# Sensors.net
KiCad netlist of a schematic drawn in Altium Designer
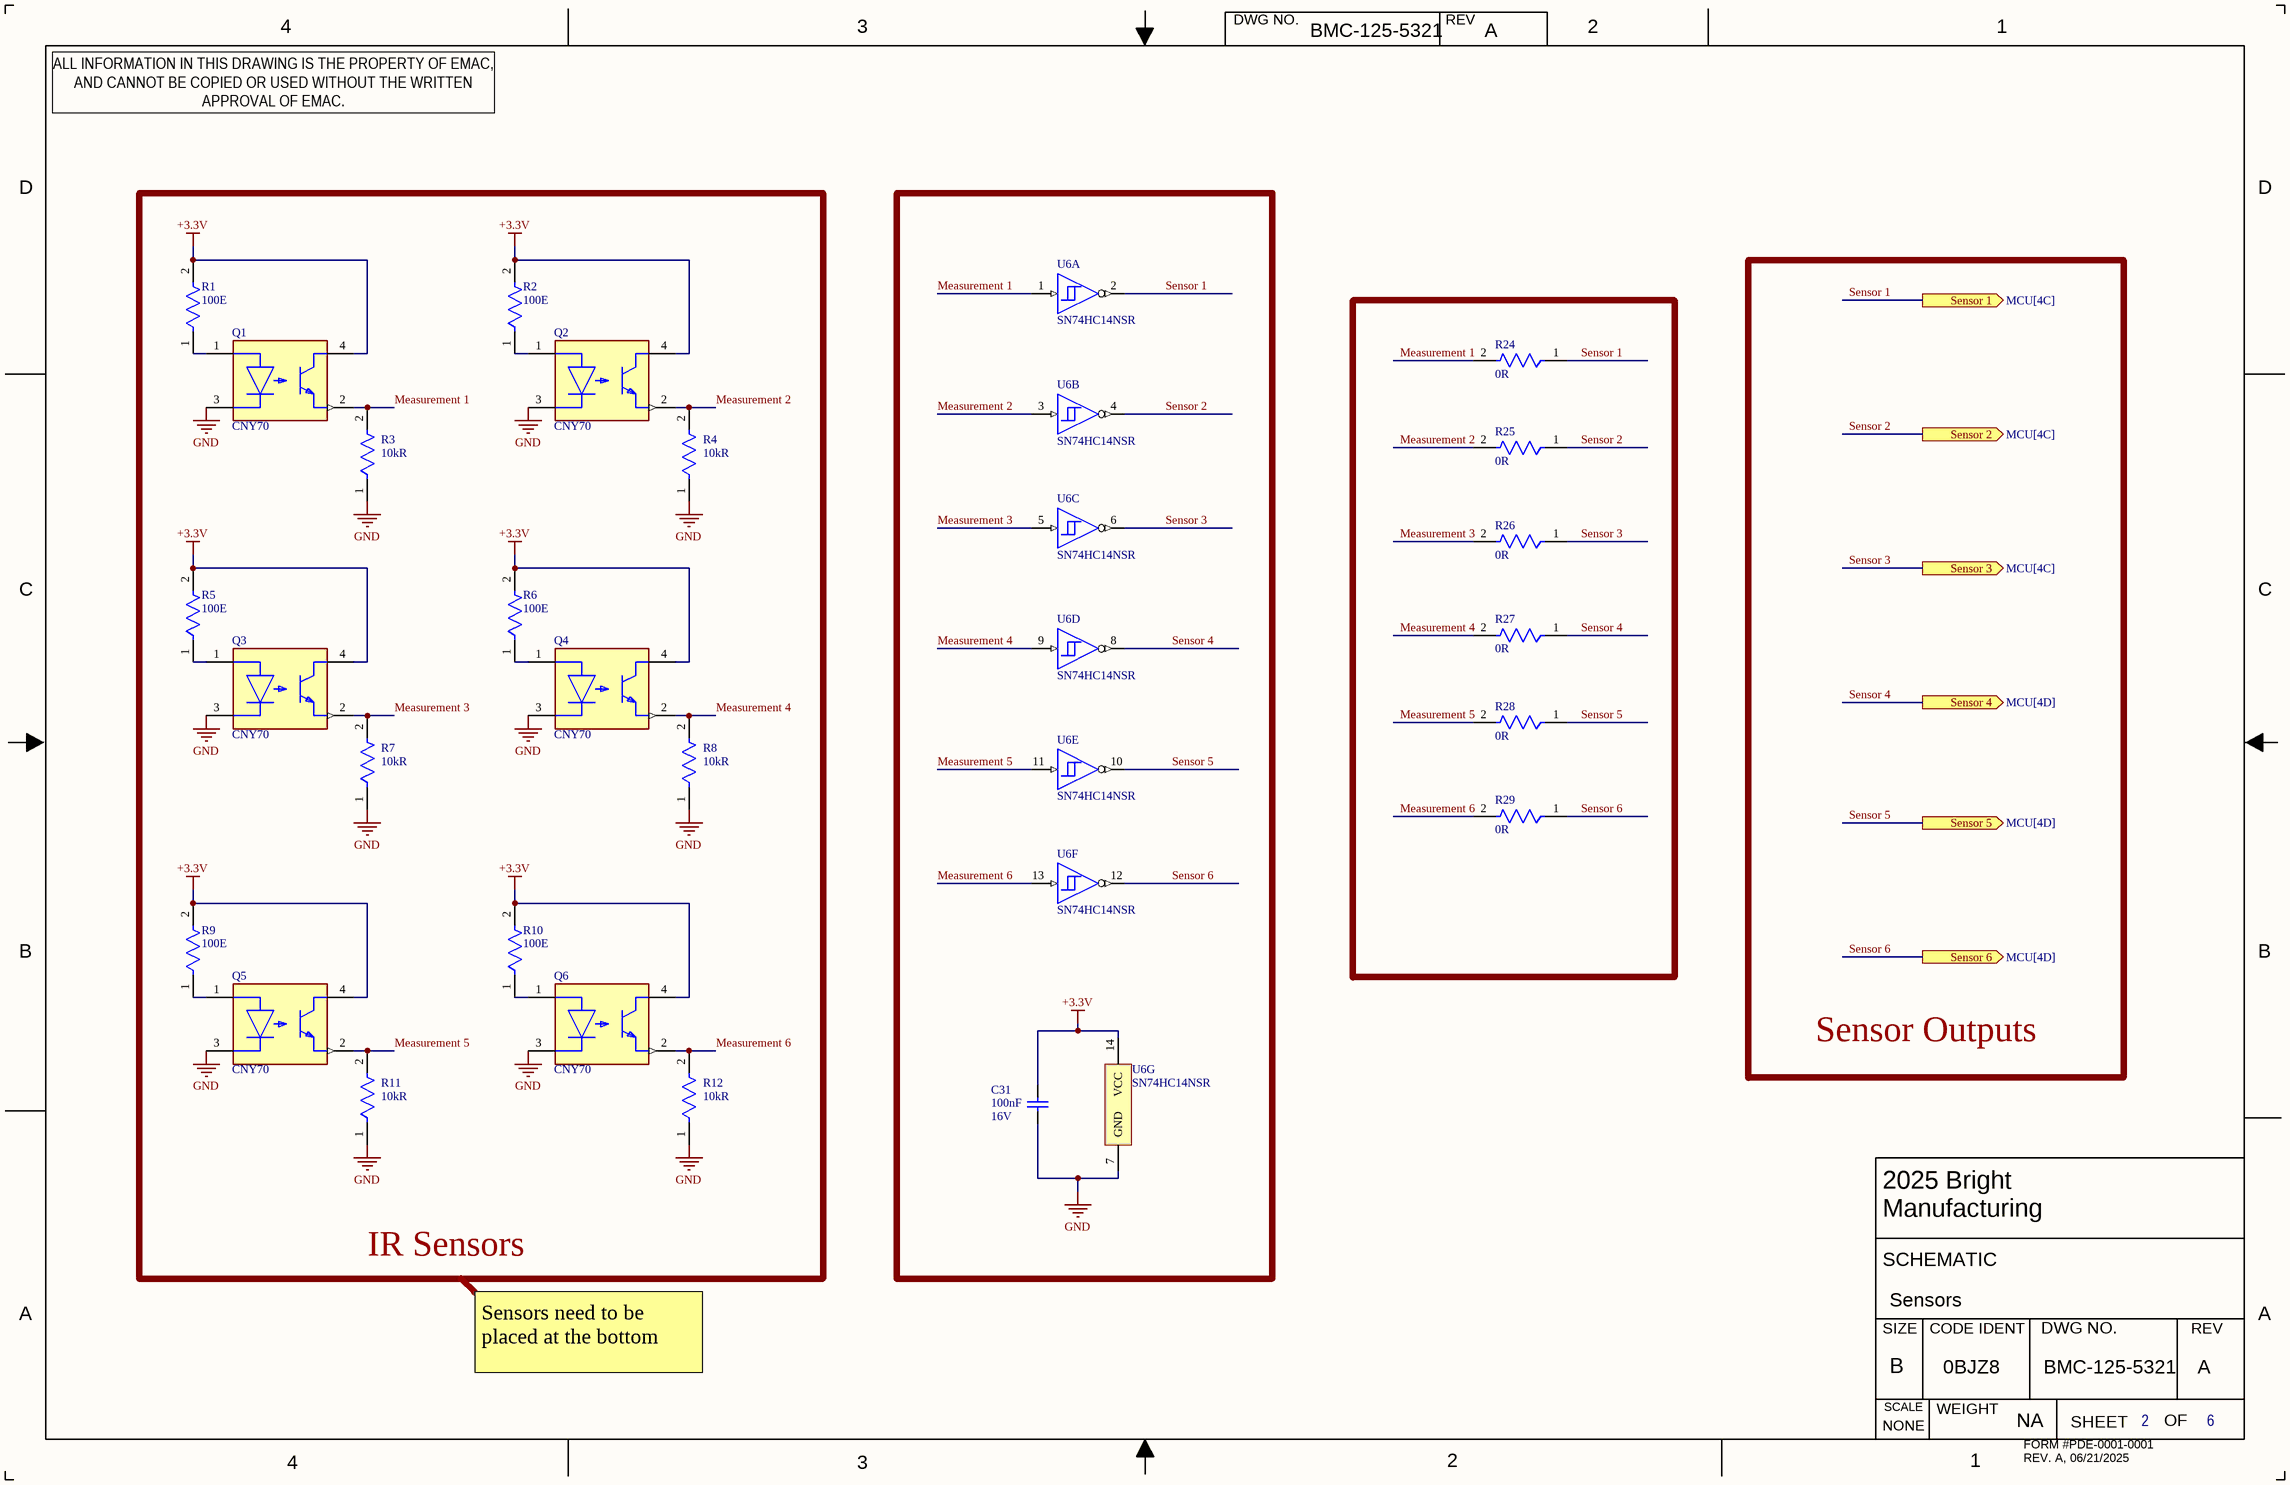
[diagram p0: Sensors.SchDoc]

(export (version "E")
  (design (tool "Eeschema 10.0.6"))
  (components
    (comp (ref "C31")
      (value "100nF")
      (footprint "CAPC1608X90X35LL15T15")
      (fields (field (name "RATED DC VOLTAGE (URDC)") "16V") (field (name "Comment") "0.1uF 16V 0603"))
      (libsource (lib "2025 Bright Manufacturing Challenge") (part "CAP"))
    )
    (comp (ref "Q1")
      (value "CNY70")
      (footprint "FP-6_544-5062_01-4-MFG")
      (description "Diffuse Photoelectric Sensor, 0mm Min, 5mm Max, 0.30-1mA, 1-Channel, Square, Through Hole Mount")
      (libsource (lib "2025 Bright Manufacturing Challenge") (part "76cf3928268f24b4c386281b57b36cb"))
    )
    (comp (ref "Q2")
      (value "CNY70")
      (footprint "FP-6_544-5062_01-4-MFG")
      (description "Diffuse Photoelectric Sensor, 0mm Min, 5mm Max, 0.30-1mA, 1-Channel, Square, Through Hole Mount")
      (libsource (lib "2025 Bright Manufacturing Challenge") (part "76cf3928268f24b4c386281b57b36cb"))
    )
    (comp (ref "Q3")
      (value "CNY70")
      (footprint "FP-6_544-5062_01-4-MFG")
      (description "Diffuse Photoelectric Sensor, 0mm Min, 5mm Max, 0.30-1mA, 1-Channel, Square, Through Hole Mount")
      (libsource (lib "2025 Bright Manufacturing Challenge") (part "76cf3928268f24b4c386281b57b36cb"))
    )
    (comp (ref "Q4")
      (value "CNY70")
      (footprint "FP-6_544-5062_01-4-MFG")
      (description "Diffuse Photoelectric Sensor, 0mm Min, 5mm Max, 0.30-1mA, 1-Channel, Square, Through Hole Mount")
      (libsource (lib "2025 Bright Manufacturing Challenge") (part "76cf3928268f24b4c386281b57b36cb"))
    )
    (comp (ref "Q5")
      (value "CNY70")
      (footprint "FP-6_544-5062_01-4-MFG")
      (description "Diffuse Photoelectric Sensor, 0mm Min, 5mm Max, 0.30-1mA, 1-Channel, Square, Through Hole Mount")
      (libsource (lib "2025 Bright Manufacturing Challenge") (part "76cf3928268f24b4c386281b57b36cb"))
    )
    (comp (ref "Q6")
      (value "CNY70")
      (footprint "FP-6_544-5062_01-4-MFG")
      (description "Diffuse Photoelectric Sensor, 0mm Min, 5mm Max, 0.30-1mA, 1-Channel, Square, Through Hole Mount")
      (libsource (lib "2025 Bright Manufacturing Challenge") (part "76cf3928268f24b4c386281b57b36cb"))
    )
    (comp (ref "R1")
      (value "100E")
      (footprint "FP-RT0603-MFG")
      (description "RES SMD 100 OHM 0.5% 1/10W 0603")
      (fields
        (field (name "TOLERANCE") "0.005")
        (field (name "OCTOPART") "https://octopart.com/rt0603dre07100rl-yageo-1441481")
      )
      (libsource (lib "Altium Content Vault") (part "1029c3af85768c4190bb7ad29bc67b5"))
    )
    (comp (ref "R2")
      (value "100E")
      (footprint "FP-RT0603-MFG")
      (description "RES SMD 100 OHM 0.5% 1/10W 0603")
      (fields
        (field (name "TOLERANCE") "0.005")
        (field (name "OCTOPART") "https://octopart.com/rt0603dre07100rl-yageo-1441481")
      )
      (libsource (lib "Altium Content Vault") (part "1029c3af85768c4190bb7ad29bc67b5"))
    )
    (comp (ref "R3")
      (value "10kR")
      (footprint "RESC1608X55X25ML10T15")
      (fields
        (field (name "TOLERANCE") "5%")
        (field (name "POWER") "100mW")
        (field (name "Comment") "10KOhm 0603")
      )
      (libsource (lib "2025 Bright Manufacturing Challenge") (part "1029c3af85768c4190bb7ad29bc67b5"))
    )
    (comp (ref "R4")
      (value "10kR")
      (footprint "RESC1608X55X25ML10T15")
      (fields
        (field (name "TOLERANCE") "5%")
        (field (name "POWER") "100mW")
        (field (name "Comment") "10KOhm 0603")
      )
      (libsource (lib "2025 Bright Manufacturing Challenge") (part "1029c3af85768c4190bb7ad29bc67b5"))
    )
    (comp (ref "R5")
      (value "100E")
      (footprint "FP-RT0603-MFG")
      (description "RES SMD 100 OHM 0.5% 1/10W 0603")
      (fields
        (field (name "TOLERANCE") "0.005")
        (field (name "OCTOPART") "https://octopart.com/rt0603dre07100rl-yageo-1441481")
      )
      (libsource (lib "Altium Content Vault") (part "1029c3af85768c4190bb7ad29bc67b5"))
    )
    (comp (ref "R6")
      (value "100E")
      (footprint "FP-RT0603-MFG")
      (description "RES SMD 100 OHM 0.5% 1/10W 0603")
      (fields
        (field (name "TOLERANCE") "0.005")
        (field (name "OCTOPART") "https://octopart.com/rt0603dre07100rl-yageo-1441481")
      )
      (libsource (lib "Altium Content Vault") (part "1029c3af85768c4190bb7ad29bc67b5"))
    )
    (comp (ref "R7")
      (value "10kR")
      (footprint "RESC1608X55X25ML10T15")
      (fields
        (field (name "TOLERANCE") "5%")
        (field (name "POWER") "100mW")
        (field (name "Comment") "10KOhm 0603")
      )
      (libsource (lib "2025 Bright Manufacturing Challenge") (part "1029c3af85768c4190bb7ad29bc67b5"))
    )
    (comp (ref "R8")
      (value "10kR")
      (footprint "RESC1608X55X25ML10T15")
      (fields
        (field (name "TOLERANCE") "5%")
        (field (name "POWER") "100mW")
        (field (name "Comment") "10KOhm 0603")
      )
      (libsource (lib "2025 Bright Manufacturing Challenge") (part "1029c3af85768c4190bb7ad29bc67b5"))
    )
    (comp (ref "R9")
      (value "100E")
      (footprint "FP-RT0603-MFG")
      (description "RES SMD 100 OHM 0.5% 1/10W 0603")
      (fields
        (field (name "TOLERANCE") "0.005")
        (field (name "OCTOPART") "https://octopart.com/rt0603dre07100rl-yageo-1441481")
      )
      (libsource (lib "Altium Content Vault") (part "1029c3af85768c4190bb7ad29bc67b5"))
    )
    (comp (ref "R10")
      (value "100E")
      (footprint "FP-RT0603-MFG")
      (description "RES SMD 100 OHM 0.5% 1/10W 0603")
      (fields
        (field (name "TOLERANCE") "0.005")
        (field (name "OCTOPART") "https://octopart.com/rt0603dre07100rl-yageo-1441481")
      )
      (libsource (lib "Altium Content Vault") (part "1029c3af85768c4190bb7ad29bc67b5"))
    )
    (comp (ref "R11")
      (value "10kR")
      (footprint "RESC1608X55X25ML10T15")
      (fields
        (field (name "TOLERANCE") "5%")
        (field (name "POWER") "100mW")
        (field (name "Comment") "10KOhm 0603")
      )
      (libsource (lib "2025 Bright Manufacturing Challenge") (part "1029c3af85768c4190bb7ad29bc67b5"))
    )
    (comp (ref "R12")
      (value "10kR")
      (footprint "RESC1608X55X25ML10T15")
      (fields
        (field (name "TOLERANCE") "5%")
        (field (name "POWER") "100mW")
        (field (name "Comment") "10KOhm 0603")
      )
      (libsource (lib "2025 Bright Manufacturing Challenge") (part "1029c3af85768c4190bb7ad29bc67b5"))
    )
    (comp (ref "R24")
      (value "0R")
      (footprint "FP-RC0603-MFG")
      (description "RES SMD 0 OHM JUMPER 1/10W 0603")
      (fields
        (field (name "TOLERANCE") "1%")
        (field (name "OCTOPART") "https://octopart.com/rc0603fr-070rl-yageo-1180803")
      )
      (libsource (lib "Altium Content Vault") (part "1029c3af85768c4190bb7ad29bc67b5"))
    )
    (comp (ref "R25")
      (value "0R")
      (footprint "FP-RC0603-MFG")
      (description "RES SMD 0 OHM JUMPER 1/10W 0603")
      (fields
        (field (name "TOLERANCE") "1%")
        (field (name "OCTOPART") "https://octopart.com/rc0603fr-070rl-yageo-1180803")
      )
      (libsource (lib "Altium Content Vault") (part "1029c3af85768c4190bb7ad29bc67b5"))
    )
    (comp (ref "R26")
      (value "0R")
      (footprint "FP-RC0603-MFG")
      (description "RES SMD 0 OHM JUMPER 1/10W 0603")
      (fields
        (field (name "TOLERANCE") "1%")
        (field (name "OCTOPART") "https://octopart.com/rc0603fr-070rl-yageo-1180803")
      )
      (libsource (lib "Altium Content Vault") (part "1029c3af85768c4190bb7ad29bc67b5"))
    )
    (comp (ref "R27")
      (value "0R")
      (footprint "FP-RC0603-MFG")
      (description "RES SMD 0 OHM JUMPER 1/10W 0603")
      (fields
        (field (name "TOLERANCE") "1%")
        (field (name "OCTOPART") "https://octopart.com/rc0603fr-070rl-yageo-1180803")
      )
      (libsource (lib "Altium Content Vault") (part "1029c3af85768c4190bb7ad29bc67b5"))
    )
    (comp (ref "R28")
      (value "0R")
      (footprint "FP-RC0603-MFG")
      (description "RES SMD 0 OHM JUMPER 1/10W 0603")
      (fields
        (field (name "TOLERANCE") "1%")
        (field (name "OCTOPART") "https://octopart.com/rc0603fr-070rl-yageo-1180803")
      )
      (libsource (lib "Altium Content Vault") (part "1029c3af85768c4190bb7ad29bc67b5"))
    )
    (comp (ref "R29")
      (value "0R")
      (footprint "FP-RC0603-MFG")
      (description "RES SMD 0 OHM JUMPER 1/10W 0603")
      (fields
        (field (name "TOLERANCE") "1%")
        (field (name "OCTOPART") "https://octopart.com/rc0603fr-070rl-yageo-1180803")
      )
      (libsource (lib "Altium Content Vault") (part "1029c3af85768c4190bb7ad29bc67b5"))
    )
    (comp (ref "U6")
      (value "SN74HC14NSR")
      (footprint "NS0014A_N")
      (description "Inverter, HC Series, 6-Func, 1-Input, CMOS, PDSO14")
      (libsource (lib "2025 Bright Manufacturing Challenge") (part "TI-CD_SNX4XXXXXX4X_19A-14-SCHMITT"))
    )
  )
  (nets
    (net (code "1") (name "+3.3V") (class "Default")
      (node (ref "C31") (pin "2") (pinfunction "2_2") (pintype "passive"))
      (node (ref "Q1") (pin "4") (pinfunction "C_4") (pintype "passive"))
      (node (ref "Q2") (pin "4") (pinfunction "C_4") (pintype "passive"))
      (node (ref "Q3") (pin "4") (pinfunction "C_4") (pintype "passive"))
      (node (ref "Q4") (pin "4") (pinfunction "C_4") (pintype "passive"))
      (node (ref "Q5") (pin "4") (pinfunction "C_4") (pintype "passive"))
      (node (ref "Q6") (pin "4") (pinfunction "C_4") (pintype "passive"))
      (node (ref "R1") (pin "2") (pinfunction "2_2") (pintype "passive"))
      (node (ref "R10") (pin "2") (pinfunction "2_2") (pintype "passive"))
      (node (ref "R2") (pin "2") (pinfunction "2_2") (pintype "passive"))
      (node (ref "R5") (pin "2") (pinfunction "2_2") (pintype "passive"))
      (node (ref "R6") (pin "2") (pinfunction "2_2") (pintype "passive"))
      (node (ref "R9") (pin "2") (pinfunction "2_2") (pintype "passive"))
      (node (ref "U6") (pin "14") (pinfunction "VCC_14") (pintype "power_in"))
    )
    (net (code "2") (name "/Measurement 1") (class "Default")
      (node (ref "Q1") (pin "2") (pinfunction "E_2") (pintype "output"))
      (node (ref "R24") (pin "2") (pinfunction "2_2") (pintype "passive"))
      (node (ref "R3") (pin "2") (pinfunction "2_2") (pintype "passive"))
      (node (ref "U6") (pin "1") (pinfunction "1A_1") (pintype "input"))
    )
    (net (code "3") (name "/Measurement 2") (class "Default")
      (node (ref "Q2") (pin "2") (pinfunction "E_2") (pintype "output"))
      (node (ref "R25") (pin "2") (pinfunction "2_2") (pintype "passive"))
      (node (ref "R4") (pin "2") (pinfunction "2_2") (pintype "passive"))
      (node (ref "U6") (pin "3") (pinfunction "2A_3") (pintype "input"))
    )
    (net (code "4") (name "/Measurement 3") (class "Default")
      (node (ref "Q3") (pin "2") (pinfunction "E_2") (pintype "output"))
      (node (ref "R26") (pin "2") (pinfunction "2_2") (pintype "passive"))
      (node (ref "R7") (pin "2") (pinfunction "2_2") (pintype "passive"))
      (node (ref "U6") (pin "5") (pinfunction "3A_5") (pintype "input"))
    )
    (net (code "5") (name "/Measurement 4") (class "Default")
      (node (ref "Q4") (pin "2") (pinfunction "E_2") (pintype "output"))
      (node (ref "R27") (pin "2") (pinfunction "2_2") (pintype "passive"))
      (node (ref "R8") (pin "2") (pinfunction "2_2") (pintype "passive"))
      (node (ref "U6") (pin "9") (pinfunction "4A_9") (pintype "input"))
    )
    (net (code "6") (name "/Measurement 5") (class "Default")
      (node (ref "Q5") (pin "2") (pinfunction "E_2") (pintype "output"))
      (node (ref "R11") (pin "2") (pinfunction "2_2") (pintype "passive"))
      (node (ref "R28") (pin "2") (pinfunction "2_2") (pintype "passive"))
      (node (ref "U6") (pin "11") (pinfunction "5A_11") (pintype "input"))
    )
    (net (code "7") (name "/Measurement 6") (class "Default")
      (node (ref "Q6") (pin "2") (pinfunction "E_2") (pintype "output"))
      (node (ref "R12") (pin "2") (pinfunction "2_2") (pintype "passive"))
      (node (ref "R29") (pin "2") (pinfunction "2_2") (pintype "passive"))
      (node (ref "U6") (pin "13") (pinfunction "6A_13") (pintype "input"))
    )
    (net (code "8") (name "/Sensor 1") (class "Default")
      (node (ref "R24") (pin "1") (pinfunction "1_1") (pintype "passive"))
      (node (ref "U6") (pin "2") (pinfunction "~{1Y}_2") (pintype "output"))
    )
    (net (code "9") (name "/Sensor 2") (class "Default")
      (node (ref "R25") (pin "1") (pinfunction "1_1") (pintype "passive"))
      (node (ref "U6") (pin "4") (pinfunction "~{2Y}_4") (pintype "output"))
    )
    (net (code "10") (name "/Sensor 3") (class "Default")
      (node (ref "R26") (pin "1") (pinfunction "1_1") (pintype "passive"))
      (node (ref "U6") (pin "6") (pinfunction "~{3Y}_6") (pintype "output"))
    )
    (net (code "11") (name "/Sensor 4") (class "Default")
      (node (ref "R27") (pin "1") (pinfunction "1_1") (pintype "passive"))
      (node (ref "U6") (pin "8") (pinfunction "~{4Y}_8") (pintype "output"))
    )
    (net (code "12") (name "/Sensor 5") (class "Default")
      (node (ref "R28") (pin "1") (pinfunction "1_1") (pintype "passive"))
      (node (ref "U6") (pin "10") (pinfunction "~{5Y}_10") (pintype "output"))
    )
    (net (code "13") (name "/Sensor 6") (class "Default")
      (node (ref "R29") (pin "1") (pinfunction "1_1") (pintype "passive"))
      (node (ref "U6") (pin "12") (pinfunction "~{6Y}_12") (pintype "output"))
    )
    (net (code "14") (name "GND") (class "Default")
      (node (ref "C31") (pin "1") (pinfunction "1_1") (pintype "passive"))
      (node (ref "Q1") (pin "3") (pinfunction "C_3") (pintype "passive"))
      (node (ref "Q2") (pin "3") (pinfunction "C_3") (pintype "passive"))
      (node (ref "Q3") (pin "3") (pinfunction "C_3") (pintype "passive"))
      (node (ref "Q4") (pin "3") (pinfunction "C_3") (pintype "passive"))
      (node (ref "Q5") (pin "3") (pinfunction "C_3") (pintype "passive"))
      (node (ref "Q6") (pin "3") (pinfunction "C_3") (pintype "passive"))
      (node (ref "R11") (pin "1") (pinfunction "1_1") (pintype "passive"))
      (node (ref "R12") (pin "1") (pinfunction "1_1") (pintype "passive"))
      (node (ref "R3") (pin "1") (pinfunction "1_1") (pintype "passive"))
      (node (ref "R4") (pin "1") (pinfunction "1_1") (pintype "passive"))
      (node (ref "R7") (pin "1") (pinfunction "1_1") (pintype "passive"))
      (node (ref "R8") (pin "1") (pinfunction "1_1") (pintype "passive"))
      (node (ref "U6") (pin "7") (pinfunction "GND_7") (pintype "power_in"))
    )
    (net (code "15") (name "Net-(Q1-A)") (class "Default")
      (node (ref "Q1") (pin "1") (pinfunction "A_1") (pintype "passive"))
      (node (ref "R1") (pin "1") (pinfunction "1_1") (pintype "passive"))
    )
    (net (code "16") (name "Net-(Q2-A)") (class "Default")
      (node (ref "Q2") (pin "1") (pinfunction "A_1") (pintype "passive"))
      (node (ref "R2") (pin "1") (pinfunction "1_1") (pintype "passive"))
    )
    (net (code "17") (name "Net-(Q3-A)") (class "Default")
      (node (ref "Q3") (pin "1") (pinfunction "A_1") (pintype "passive"))
      (node (ref "R5") (pin "1") (pinfunction "1_1") (pintype "passive"))
    )
    (net (code "18") (name "Net-(Q4-A)") (class "Default")
      (node (ref "Q4") (pin "1") (pinfunction "A_1") (pintype "passive"))
      (node (ref "R6") (pin "1") (pinfunction "1_1") (pintype "passive"))
    )
    (net (code "19") (name "Net-(Q5-A)") (class "Default")
      (node (ref "Q5") (pin "1") (pinfunction "A_1") (pintype "passive"))
      (node (ref "R9") (pin "1") (pinfunction "1_1") (pintype "passive"))
    )
    (net (code "20") (name "Net-(Q6-A)") (class "Default")
      (node (ref "Q6") (pin "1") (pinfunction "A_1") (pintype "passive"))
      (node (ref "R10") (pin "1") (pinfunction "1_1") (pintype "passive"))
    )
  )
)
